# Switched_Power.net
KiCad netlist of a schematic drawn in Altium Designer
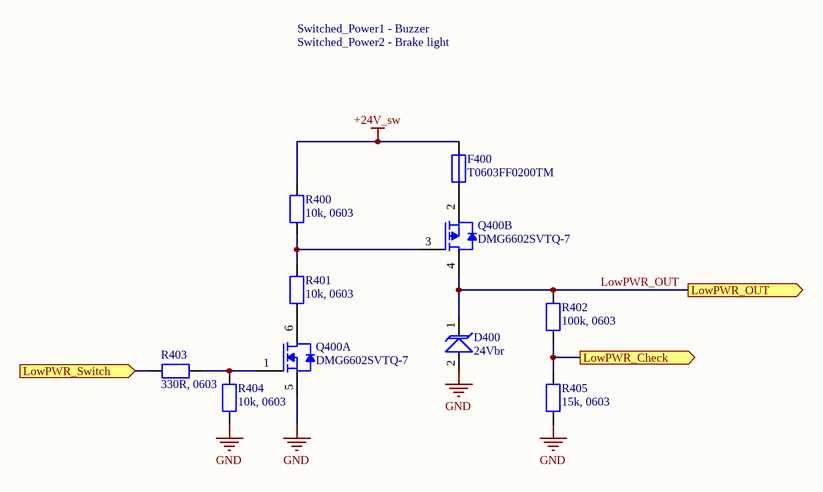
[diagram p0: Switched_Power.SchDoc]

(export (version "E")
  (design (tool "Eeschema 10.0.6"))
  (components
    (comp (ref "D400")
      (value "24Vbr")
      (footprint "SOD-123W")
      (description "Trans Voltage Suppressor Diode, 400W, 24V V(RWM), Unidirectional, 1 Element, Silicon")
      (fields
        (field (name "MANUFACTURER PART NUMBER") "PTVS24VS1UR,115")
        (field (name "MANUFACTURER") "Nexperia")
      )
      (libsource (lib "Formula Student Team Tallinn (Estonia)") (part "Diode TVS"))
    )
    (comp (ref "F400")
      (value "T0603FF0200TM")
      (footprint "FUSE [0603] 1608")
      (description "Fuse, Very Fast Act, 0.2A, 65VDC, 0603 Rohs Compliant: Yes")
      (libsource (lib "Formula Student Team Tallinn (Estonia)") (part "Fuse"))
    )
    (comp (ref "Q400")
      (value "DMG6602SVTQ-7")
      (footprint "SOT23-6")
      (libsource (lib "Formula Student Team Tallinn (Estonia)") (part "Dual MOSFET P&N channel"))
    )
    (comp (ref "R400")
      (value "10k, 0603")
      (footprint "RES [0603] 1608")
      (description "Standard resistor part")
      (libsource (lib "Formula Student Team Tallinn (Estonia)") (part "Resistor"))
    )
    (comp (ref "R401")
      (value "10k, 0603")
      (footprint "RES [0603] 1608")
      (description "Standard resistor part")
      (libsource (lib "Formula Student Team Tallinn (Estonia)") (part "Resistor"))
    )
    (comp (ref "R402")
      (value "100k, 0603")
      (footprint "RES [0603] 1608")
      (description "Standard resistor part")
      (libsource (lib "Formula Student Team Tallinn (Estonia)") (part "Resistor"))
    )
    (comp (ref "R403")
      (value "330R, 0603")
      (footprint "RES [0603] 1608")
      (description "Standard resistor part")
      (libsource (lib "Formula Student Team Tallinn (Estonia)") (part "Resistor"))
    )
    (comp (ref "R404")
      (value "10k, 0603")
      (footprint "RES [0603] 1608")
      (description "Standard resistor part")
      (libsource (lib "Formula Student Team Tallinn (Estonia)") (part "Resistor"))
    )
    (comp (ref "R405")
      (value "15k, 0603")
      (footprint "RES [0603] 1608")
      (description "Standard resistor part")
      (libsource (lib "Formula Student Team Tallinn (Estonia)") (part "Resistor"))
    )
  )
  (nets
    (net (code "1") (name "+24V_sw") (class "Default")
      (node (ref "F400") (pin "2") (pinfunction "2_2") (pintype "passive"))
      (node (ref "R400") (pin "2") (pinfunction "2_2") (pintype "passive"))
    )
    (net (code "2") (name "/LowPWR_Check") (class "Default")
      (node (ref "R402") (pin "1") (pinfunction "1_1") (pintype "passive"))
      (node (ref "R405") (pin "2") (pinfunction "2_2") (pintype "passive"))
    )
    (net (code "3") (name "/LowPWR_OUT") (class "Default")
      (node (ref "D400") (pin "1") (pinfunction "K_1") (pintype "passive"))
      (node (ref "Q400") (pin "4") (pinfunction "D_4") (pintype "passive"))
      (node (ref "R402") (pin "2") (pinfunction "2_2") (pintype "passive"))
    )
    (net (code "4") (name "/LowPWR_Switch") (class "Default")
      (node (ref "R403") (pin "2") (pinfunction "2_2") (pintype "passive"))
    )
    (net (code "5") (name "GND") (class "Default")
      (node (ref "D400") (pin "2") (pinfunction "A_2") (pintype "passive"))
      (node (ref "Q400") (pin "5") (pinfunction "S_5") (pintype "passive"))
      (node (ref "R404") (pin "1") (pinfunction "1_1") (pintype "passive"))
      (node (ref "R405") (pin "1") (pinfunction "1_1") (pintype "passive"))
    )
    (net (code "6") (name "Net-(Q400A-D)") (class "Default")
      (node (ref "Q400") (pin "6") (pinfunction "D_6") (pintype "passive"))
      (node (ref "R401") (pin "1") (pinfunction "1_1") (pintype "passive"))
    )
    (net (code "7") (name "Net-(Q400A-G)") (class "Default")
      (node (ref "Q400") (pin "1") (pinfunction "G_1") (pintype "passive"))
      (node (ref "R403") (pin "1") (pinfunction "1_1") (pintype "passive"))
      (node (ref "R404") (pin "2") (pinfunction "2_2") (pintype "passive"))
    )
    (net (code "8") (name "Net-(Q400B-G)") (class "Default")
      (node (ref "Q400") (pin "3") (pinfunction "G_3") (pintype "passive"))
      (node (ref "R400") (pin "1") (pinfunction "1_1") (pintype "passive"))
      (node (ref "R401") (pin "2") (pinfunction "2_2") (pintype "passive"))
    )
    (net (code "9") (name "Net-(Q400B-S)") (class "Default")
      (node (ref "F400") (pin "1") (pinfunction "1_1") (pintype "passive"))
      (node (ref "Q400") (pin "2") (pinfunction "S_2") (pintype "passive"))
    )
  )
)
